# VOLT_SW.net
KiCad netlist of a schematic drawn in Altium Designer
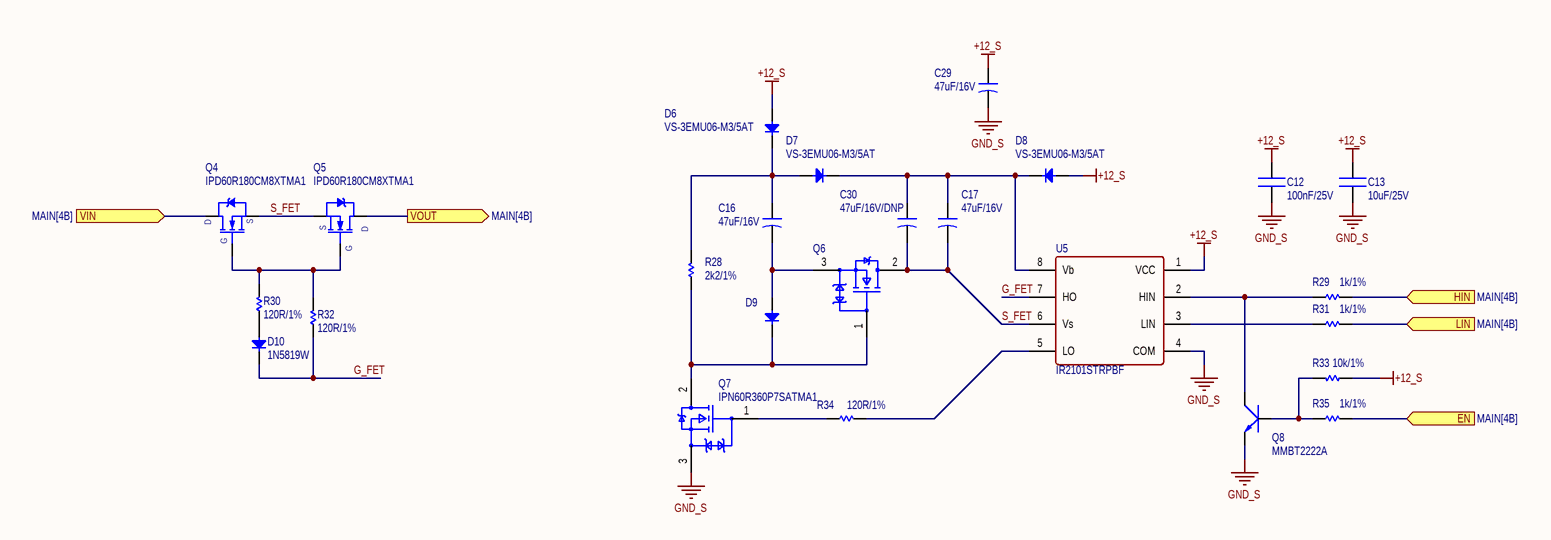
[diagram p0: VOLT_SW.SchDoc]

(export (version "E")
  (design (tool "Eeschema 10.0.6"))
  (components
    (comp (ref "C12")
      (value "100nF/25V")
      (footprint "CN-SMD-0603")
      (description "CL10B104KA8NNNC")
      (libsource (lib "Library") (part "CN"))
    )
    (comp (ref "C13")
      (value "10uF/25V")
      (footprint "CN-SMD-0603")
      (description "0603W106M250XD")
      (libsource (lib "Library") (part "CN"))
    )
    (comp (ref "C16")
      (value "47uF/16V")
      (footprint "Tantalum 1210")
      (description "TCNT476M016R0200")
      (fields (field (name "PUBLISHER") "Altium Limited"))
      (libsource (lib "Library") (part "CN-SMD"))
    )
    (comp (ref "C17")
      (value "47uF/16V")
      (footprint "Tantalum 1210")
      (description "TCNT476M016R0200")
      (fields (field (name "PUBLISHER") "Altium Limited"))
      (libsource (lib "Library") (part "CN-SMD"))
    )
    (comp (ref "C29")
      (value "47uF/16V")
      (footprint "Tantalum 1210")
      (description "TCNT476M016R0200")
      (fields (field (name "PUBLISHER") "Altium Limited"))
      (libsource (lib "Library") (part "CN-SMD"))
    )
    (comp (ref "C30")
      (value "47uF/16V/DNP")
      (footprint "Tantalum 1210")
      (description "TCNT476M016R0200/DNP")
      (fields (field (name "PUBLISHER") "Altium Limited"))
      (libsource (lib "Library") (part "CN-SMD"))
    )
    (comp (ref "D6")
      (value "VS-3EMU06-M3/5AT")
      (footprint "DIO-SMD-A")
      (fields (field (name "PUBLISHER") "Altium Limited"))
      (libsource (lib "Library") (part "Diode SMD"))
    )
    (comp (ref "D7")
      (value "VS-3EMU06-M3/5AT")
      (footprint "DIO-SMD-A")
      (fields (field (name "PUBLISHER") "Altium Limited"))
      (libsource (lib "Library") (part "Diode SMD"))
    )
    (comp (ref "D8")
      (value "VS-3EMU06-M3/5AT")
      (footprint "DIO-SMD-A")
      (fields (field (name "PUBLISHER") "Altium Limited"))
      (libsource (lib "Library") (part "Diode SMD"))
    )
    (comp (ref "D9")
      (value "VS-3EMU06-M3/5AT")
      (footprint "DIO-SMD-A")
      (fields (field (name "PUBLISHER") "Altium Limited"))
      (libsource (lib "Library") (part "Diode SMD"))
    )
    (comp (ref "D10")
      (value "1N5819W")
      (footprint "DIO-SMD-123")
      (fields (field (name "PUBLISHER") "Altium Limited"))
      (libsource (lib "Library") (part "Diode SMD"))
    )
    (comp (ref "Q4")
      (value "IPD60R180CM8XTMA1")
      (footprint "TO252-123")
      (libsource (lib "Library") (part "FDD8870"))
    )
    (comp (ref "Q5")
      (value "IPD60R180CM8XTMA1")
      (footprint "TO252-123")
      (libsource (lib "Library") (part "FDD8870"))
    )
    (comp (ref "Q6")
      (value "IPN60R360P7SATMA1")
      (footprint "SOT223-3")
      (fields
        (field (name "MANUFACTURER") "Infineon")
        (field (name "OCTOPART") "https://octopart.com/ipn60r360p7satma1-infineon-84309560")
      )
      (libsource (lib "Library") (part "IPN60R360P7SATMA1"))
    )
    (comp (ref "Q7")
      (value "IPN60R360P7SATMA1")
      (footprint "SOT223-3")
      (fields
        (field (name "MANUFACTURER") "Infineon")
        (field (name "OCTOPART") "https://octopart.com/ipn60r360p7satma1-infineon-84309560")
      )
      (libsource (lib "Library") (part "IPN60R360P7SATMA1"))
    )
    (comp (ref "Q8") (value "MMBT2222A") (footprint "SOT23-132") (libsource (lib "Library") (part "2SC1815")))
    (comp (ref "R28")
      (value "2k2/1%")
      (footprint "RES-SMD-0603")
      (description "ERJ-3EKF2201V")
      (fields
        (field (name "MANUFACTURER") "Generic Components")
        (field (name "PUBLISHER") "Altium Hobart Technology Centre")
      )
      (libsource (lib "Library") (part "Res-SMD"))
    )
    (comp (ref "R29")
      (value "1k/1%")
      (footprint "RES-SMD-0603")
      (description "ERJ-3EKF1001V")
      (fields
        (field (name "MANUFACTURER") "Generic Components")
        (field (name "PUBLISHER") "Altium Hobart Technology Centre")
      )
      (libsource (lib "Library") (part "Res-SMD"))
    )
    (comp (ref "R30")
      (value "120R/1%")
      (footprint "RES-SMD-0603")
      (description "ERJ-3EKF1200V")
      (fields
        (field (name "MANUFACTURER") "Generic Components")
        (field (name "PUBLISHER") "Altium Hobart Technology Centre")
      )
      (libsource (lib "Library") (part "Res-SMD"))
    )
    (comp (ref "R31")
      (value "1k/1%")
      (footprint "RES-SMD-0603")
      (description "ERJ-3EKF1001V")
      (fields
        (field (name "MANUFACTURER") "Generic Components")
        (field (name "PUBLISHER") "Altium Hobart Technology Centre")
      )
      (libsource (lib "Library") (part "Res-SMD"))
    )
    (comp (ref "R32")
      (value "120R/1%")
      (footprint "RES-SMD-0603")
      (description "ERJ-3EKF1200V")
      (fields
        (field (name "MANUFACTURER") "Generic Components")
        (field (name "PUBLISHER") "Altium Hobart Technology Centre")
      )
      (libsource (lib "Library") (part "Res-SMD"))
    )
    (comp (ref "R33")
      (value "10k/1%")
      (footprint "RES-SMD-0603")
      (description "ERJ-3EKF1002V")
      (fields
        (field (name "MANUFACTURER") "Generic Components")
        (field (name "PUBLISHER") "Altium Hobart Technology Centre")
      )
      (libsource (lib "Library") (part "Res-SMD"))
    )
    (comp (ref "R34")
      (value "120R/1%")
      (footprint "RES-SMD-0603")
      (description "ERJ-3EKF1200V")
      (fields
        (field (name "MANUFACTURER") "Generic Components")
        (field (name "PUBLISHER") "Altium Hobart Technology Centre")
      )
      (libsource (lib "Library") (part "Res-SMD"))
    )
    (comp (ref "R35")
      (value "1k/1%")
      (footprint "RES-SMD-0603")
      (description "ERJ-3EKF1001V")
      (fields
        (field (name "MANUFACTURER") "Generic Components")
        (field (name "PUBLISHER") "Altium Hobart Technology Centre")
      )
      (libsource (lib "Library") (part "Res-SMD"))
    )
    (comp (ref "U5") (value "IR2101STRPBF") (footprint "SO8") (libsource (lib "Library") (part "IR2101S")))
  )
  (nets
    (net (code "1") (name "+12_S") (class "Default")
      (node (ref "C12") (pin "2") (pinfunction "2_2") (pintype "passive"))
      (node (ref "C13") (pin "2") (pinfunction "2_2") (pintype "passive"))
      (node (ref "C29") (pin "1") (pinfunction "1_1") (pintype "passive"))
      (node (ref "D6") (pin "1") (pinfunction "A_1") (pintype "passive"))
      (node (ref "D8") (pin "1") (pinfunction "A_1") (pintype "passive"))
      (node (ref "R33") (pin "1") (pinfunction "1_1") (pintype "passive"))
      (node (ref "U5") (pin "1") (pinfunction "VCC_1") (pintype "passive"))
    )
    (net (code "2") (name "/EN") (class "Default")
      (node (ref "R35") (pin "1") (pinfunction "1_1") (pintype "passive"))
    )
    (net (code "3") (name "/G_FET") (class "Default")
      (node (ref "D10") (pin "2") (pinfunction "K_2") (pintype "passive"))
      (node (ref "R32") (pin "1") (pinfunction "1_1") (pintype "passive"))
      (node (ref "U5") (pin "7") (pinfunction "HO_7") (pintype "passive"))
    )
    (net (code "4") (name "/HIN") (class "Default")
      (node (ref "R29") (pin "1") (pinfunction "1_1") (pintype "passive"))
    )
    (net (code "5") (name "/LIN") (class "Default")
      (node (ref "R31") (pin "1") (pinfunction "1_1") (pintype "passive"))
    )
    (net (code "6") (name "/S_FET") (class "Default")
      (node (ref "C17") (pin "2") (pinfunction "2_2") (pintype "passive"))
      (node (ref "C30") (pin "2") (pinfunction "2_2") (pintype "passive"))
      (node (ref "Q4") (pin "3") (pinfunction "S_3") (pintype "passive"))
      (node (ref "Q5") (pin "3") (pinfunction "S_3") (pintype "passive"))
      (node (ref "Q6") (pin "2") (pinfunction "Drain_2") (pintype "passive"))
      (node (ref "U5") (pin "6") (pinfunction "Vs_6") (pintype "passive"))
    )
    (net (code "7") (name "/VIN") (class "Default")
      (node (ref "Q4") (pin "2") (pinfunction "D_2") (pintype "passive"))
    )
    (net (code "8") (name "/VOUT") (class "Default")
      (node (ref "Q5") (pin "2") (pinfunction "D_2") (pintype "passive"))
    )
    (net (code "9") (name "GND_S") (class "Default")
      (node (ref "C12") (pin "1") (pinfunction "1_1") (pintype "passive"))
      (node (ref "C13") (pin "1") (pinfunction "1_1") (pintype "passive"))
      (node (ref "C29") (pin "2") (pinfunction "2_2") (pintype "passive"))
      (node (ref "Q7") (pin "3") (pinfunction "Source_3") (pintype "passive"))
      (node (ref "Q8") (pin "2") (pinfunction "E_2") (pintype "passive"))
      (node (ref "U5") (pin "4") (pinfunction "COM_4") (pintype "passive"))
    )
    (net (code "10") (name "Net-(D6-K)") (class "Default")
      (node (ref "C16") (pin "1") (pinfunction "1_1") (pintype "passive"))
      (node (ref "D6") (pin "2") (pinfunction "K_2") (pintype "passive"))
      (node (ref "D7") (pin "1") (pinfunction "A_1") (pintype "passive"))
      (node (ref "R28") (pin "2") (pinfunction "2_2") (pintype "passive"))
    )
    (net (code "11") (name "Net-(D7-K)") (class "Default")
      (node (ref "C17") (pin "1") (pinfunction "1_1") (pintype "passive"))
      (node (ref "C30") (pin "1") (pinfunction "1_1") (pintype "passive"))
      (node (ref "D7") (pin "2") (pinfunction "K_2") (pintype "passive"))
      (node (ref "D8") (pin "2") (pinfunction "K_2") (pintype "passive"))
      (node (ref "U5") (pin "8") (pinfunction "Vb_8") (pintype "passive"))
    )
    (net (code "12") (name "Net-(D9-A)") (class "Default")
      (node (ref "C16") (pin "2") (pinfunction "2_2") (pintype "passive"))
      (node (ref "D9") (pin "1") (pinfunction "A_1") (pintype "passive"))
      (node (ref "Q6") (pin "3") (pinfunction "Source_3") (pintype "passive"))
    )
    (net (code "13") (name "Net-(D9-K)") (class "Default")
      (node (ref "D9") (pin "2") (pinfunction "K_2") (pintype "passive"))
      (node (ref "Q6") (pin "1") (pinfunction "Gate_1") (pintype "passive"))
      (node (ref "Q7") (pin "2") (pinfunction "Drain_2") (pintype "passive"))
      (node (ref "R28") (pin "1") (pinfunction "1_1") (pintype "passive"))
    )
    (net (code "14") (name "Net-(D10-A)") (class "Default")
      (node (ref "D10") (pin "1") (pinfunction "A_1") (pintype "passive"))
      (node (ref "R30") (pin "1") (pinfunction "1_1") (pintype "passive"))
    )
    (net (code "15") (name "Net-(Q4-G)") (class "Default")
      (node (ref "Q4") (pin "1") (pinfunction "G_1") (pintype "passive"))
      (node (ref "Q5") (pin "1") (pinfunction "G_1") (pintype "passive"))
      (node (ref "R30") (pin "2") (pinfunction "2_2") (pintype "passive"))
      (node (ref "R32") (pin "2") (pinfunction "2_2") (pintype "passive"))
    )
    (net (code "16") (name "Net-(Q7-Gate)") (class "Default")
      (node (ref "Q7") (pin "1") (pinfunction "Gate_1") (pintype "passive"))
      (node (ref "R34") (pin "1") (pinfunction "1_1") (pintype "passive"))
    )
    (net (code "17") (name "Net-(Q8-B)") (class "Default")
      (node (ref "Q8") (pin "1") (pinfunction "B_1") (pintype "passive"))
      (node (ref "R33") (pin "2") (pinfunction "2_2") (pintype "passive"))
      (node (ref "R35") (pin "2") (pinfunction "2_2") (pintype "passive"))
    )
    (net (code "18") (name "Net-(Q8-C)") (class "Default")
      (node (ref "Q8") (pin "3") (pinfunction "C_3") (pintype "passive"))
      (node (ref "R29") (pin "2") (pinfunction "2_2") (pintype "passive"))
      (node (ref "U5") (pin "2") (pinfunction "HIN_2") (pintype "passive"))
    )
    (net (code "19") (name "Net-(U5-LIN)") (class "Default")
      (node (ref "R31") (pin "2") (pinfunction "2_2") (pintype "passive"))
      (node (ref "U5") (pin "3") (pinfunction "LIN_3") (pintype "passive"))
    )
    (net (code "20") (name "Net-(U5-LO)") (class "Default")
      (node (ref "R34") (pin "2") (pinfunction "2_2") (pintype "passive"))
      (node (ref "U5") (pin "5") (pinfunction "LO_5") (pintype "passive"))
    )
  )
)
